# robot_sumo_easyeda.net
KiCad netlist of a schematic drawn in EasyEDA
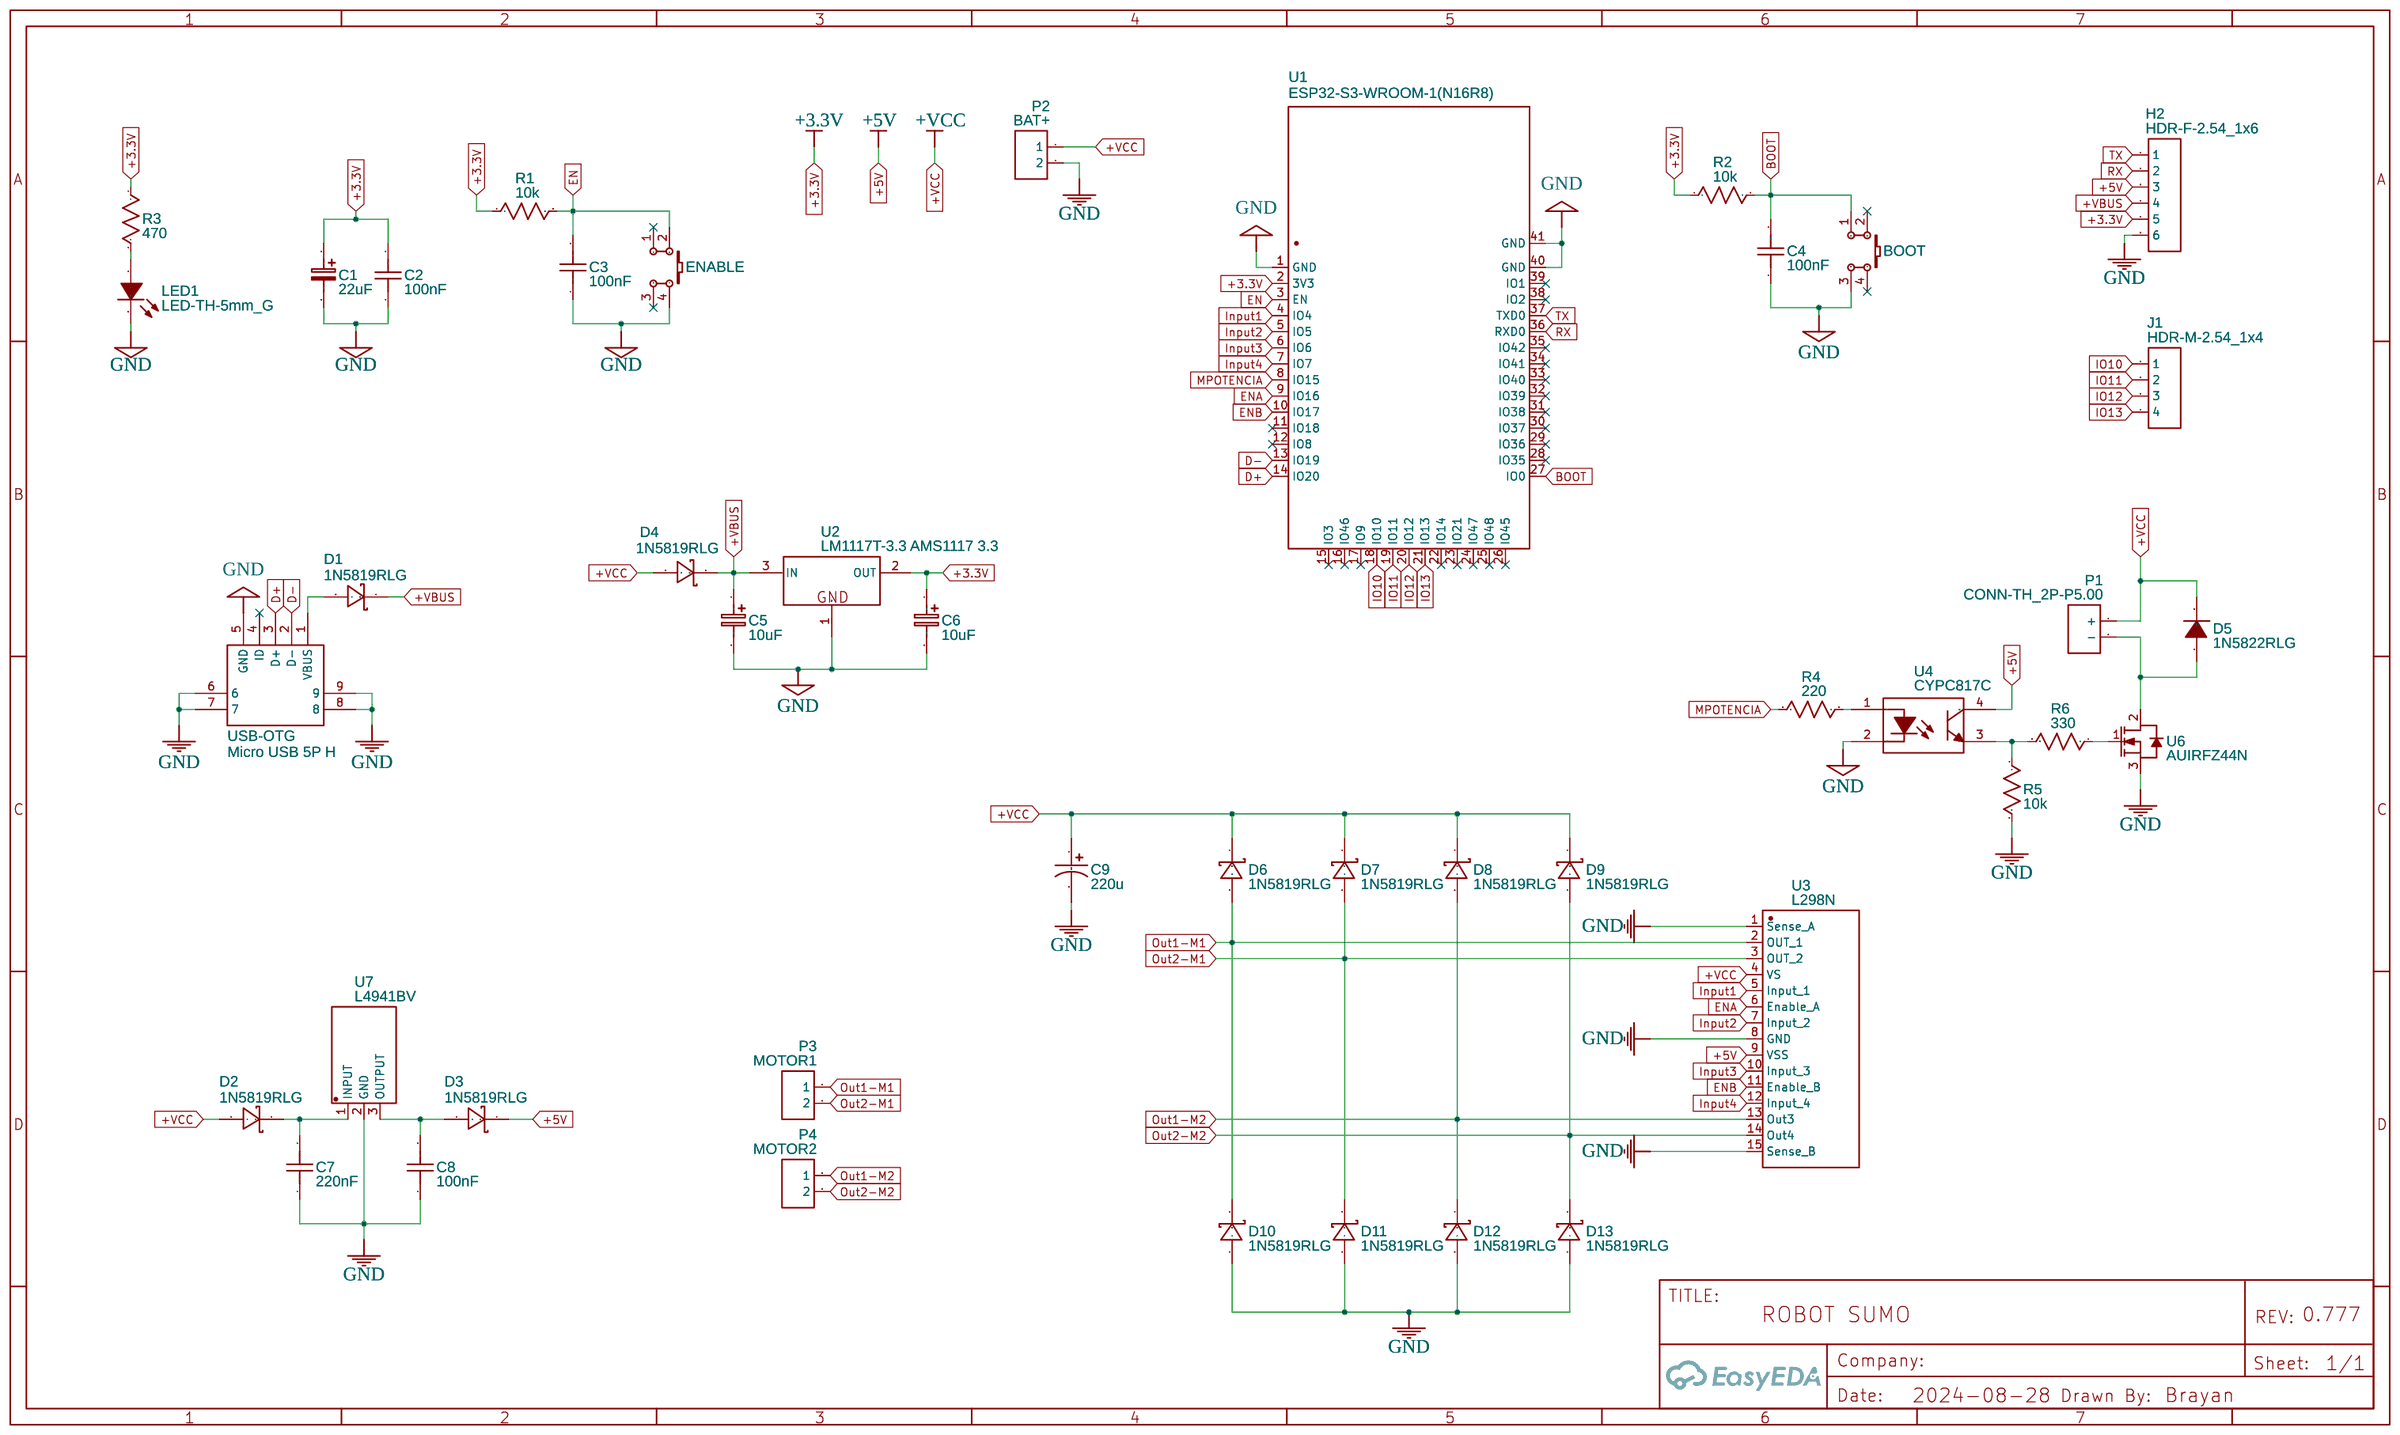
[diagram p0: schematic sheet]

(export (version "E")
  (design (tool "Eeschema 10.0.6"))
  (components
    (comp (ref "BOOT")
      (value "K4-6×6_TH")
      (fields (field (name "Manufacturer Part") "K2-1102DP-E4SW-04") (field (name "Manufacturer") "韩国韩荣"))
      (libsource (lib "") (part "K4-6×6_TH_1"))
    )
    (comp (ref "C1") (value "22uF") (libsource (lib "") (part "CE_TH_D5.0×F2.0_EU_2")))
    (comp (ref "C2")
      (value "100nF")
      (fields
        (field (name "Manufacturer Part") "CC1E104ZA1FD3F5O10MF")
        (field (name "Manufacturer") "Dersonic(德尔创)")
      )
      (libsource (lib "") (part "CC1E104ZA1FD3F5O10MF"))
    )
    (comp (ref "C3")
      (value "100nF")
      (fields
        (field (name "Manufacturer Part") "CC1E104ZA1FD3F5O10MF")
        (field (name "Manufacturer") "Dersonic(德尔创)")
      )
      (libsource (lib "") (part "CC1E104ZA1FD3F5O10MF"))
    )
    (comp (ref "C4")
      (value "100nF")
      (fields
        (field (name "Manufacturer Part") "CC1E104ZA1FD3F5O10MF")
        (field (name "Manufacturer") "Dersonic(德尔创)")
      )
      (libsource (lib "") (part "CC1E104ZA1FD3F5O10MF"))
    )
    (comp (ref "C5") (value "10uF") (libsource (lib "") (part "CE_TH_D5.0×F2.0_EU_1")))
    (comp (ref "C6") (value "10uF") (libsource (lib "") (part "CE_TH_D5.0×F2.0_EU")))
    (comp (ref "C7")
      (value "220nF")
      (fields
        (field (name "Manufacturer Part") "CC1E104ZA1FD3F5O10MF")
        (field (name "Manufacturer") "Dersonic(德尔创)")
      )
      (libsource (lib "") (part "CC1E104ZA1FD3F5O10MF"))
    )
    (comp (ref "C8")
      (value "100nF")
      (fields
        (field (name "Manufacturer Part") "CC1E104ZA1FD3F5O10MF")
        (field (name "Manufacturer") "Dersonic(德尔创)")
      )
      (libsource (lib "") (part "CC1E104ZA1FD3F5O10MF"))
    )
    (comp (ref "C9") (value "220u") (libsource (lib "") (part "CE_TH_D8.0×F3.5_US")))
    (comp (ref "D1")
      (value "1N5819RLG")
      (fields (field (name "Manufacturer") "onsemi(安森美)"))
      (libsource (lib "") (part "1N5819RLG"))
    )
    (comp (ref "D2")
      (value "1N5819RLG")
      (fields (field (name "Manufacturer") "onsemi(安森美)"))
      (libsource (lib "") (part "1N5819RLG"))
    )
    (comp (ref "D3")
      (value "1N5819RLG")
      (fields (field (name "Manufacturer") "onsemi(安森美)"))
      (libsource (lib "") (part "1N5819RLG"))
    )
    (comp (ref "D4")
      (value "1N5819RLG")
      (fields (field (name "Manufacturer") "onsemi(安森美)"))
      (libsource (lib "") (part "1N5819RLG"))
    )
    (comp (ref "D5")
      (value "1N5822RLG")
      (fields (field (name "Manufacturer") "onsemi(安森美)"))
      (libsource (lib "") (part "1N5822RLG"))
    )
    (comp (ref "D6")
      (value "1N5819RLG")
      (fields (field (name "Manufacturer") "onsemi(安森美)"))
      (libsource (lib "") (part "1N5819RLG_1"))
    )
    (comp (ref "D7")
      (value "1N5819RLG")
      (fields (field (name "Manufacturer") "onsemi(安森美)"))
      (libsource (lib "") (part "1N5819RLG_1"))
    )
    (comp (ref "D8")
      (value "1N5819RLG")
      (fields (field (name "Manufacturer") "onsemi(安森美)"))
      (libsource (lib "") (part "1N5819RLG_1"))
    )
    (comp (ref "D9")
      (value "1N5819RLG")
      (fields (field (name "Manufacturer") "onsemi(安森美)"))
      (libsource (lib "") (part "1N5819RLG_1"))
    )
    (comp (ref "D10")
      (value "1N5819RLG")
      (fields (field (name "Manufacturer") "onsemi(安森美)"))
      (libsource (lib "") (part "1N5819RLG_1"))
    )
    (comp (ref "D11")
      (value "1N5819RLG")
      (fields (field (name "Manufacturer") "onsemi(安森美)"))
      (libsource (lib "") (part "1N5819RLG_1"))
    )
    (comp (ref "D12")
      (value "1N5819RLG")
      (fields (field (name "Manufacturer") "onsemi(安森美)"))
      (libsource (lib "") (part "1N5819RLG_1"))
    )
    (comp (ref "D13")
      (value "1N5819RLG")
      (fields (field (name "Manufacturer") "onsemi(安森美)"))
      (libsource (lib "") (part "1N5819RLG_1"))
    )
    (comp (ref "ENABLE")
      (value "K4-6×6_TH")
      (fields (field (name "Manufacturer Part") "K2-1102DP-E4SW-04") (field (name "Manufacturer") "韩国韩荣"))
      (libsource (lib "") (part "K4-6×6_TH"))
    )
    (comp (ref "H2") (value "HDR-F-2.54_1x6") (libsource (lib "") (part "HDR-F-2.54_1x6")))
    (comp (ref "J1") (value "HDR-M-2.54_1x4") (libsource (lib "") (part "HDR-M-2.54_1x4")))
    (comp (ref "LED1")
      (value "LED-TH-5mm_G")
      (fields
        (field (name "Manufacturer Part") "333-2SYGD/S530-E2")
        (field (name "Manufacturer") "EVERLIGHT(台湾亿光)")
      )
      (libsource (lib "") (part "LED-TH-5mm_G"))
    )
    (comp (ref "P1") (value "CONN-TH_2P-P5.00") (libsource (lib "") (part "CONN-TH_2P-P5.00")))
    (comp (ref "P2") (value "BAT+") (libsource (lib "") (part "CONN-TH_2P-P5.00_1")))
    (comp (ref "P3") (value "MOTOR1") (libsource (lib "") (part "CONN-TH_2P-P5.00_1")))
    (comp (ref "P4") (value "MOTOR2") (libsource (lib "") (part "CONN-TH_2P-P5.00_1")))
    (comp (ref "R1") (value "10k") (libsource (lib "") (part "R_AXIAL-0.4_US_2")))
    (comp (ref "R2") (value "10k") (libsource (lib "") (part "R_AXIAL-0.4_US_2")))
    (comp (ref "R3") (value "470") (libsource (lib "") (part "R_AXIAL-0.4_US")))
    (comp (ref "R4") (value "220") (libsource (lib "") (part "R_AXIAL-0.4_US_1")))
    (comp (ref "R5") (value "10k") (libsource (lib "") (part "R_AXIAL-0.4_US")))
    (comp (ref "R6") (value "330") (libsource (lib "") (part "R_AXIAL-0.4_US_1")))
    (comp (ref "U1")
      (value "ESP32-S3-WROOM-1(N16R8)")
      (fields
        (field (name "Manufacturer Part") "ESP32-S3-WROOM-1-N16R8")
        (field (name "Manufacturer") "ESPRESSIF(乐鑫)")
      )
      (libsource (lib "") (part "ESP32-S3-WROOM-1(N16R8)"))
    )
    (comp (ref "U2")
      (value "LM1117T-3.3 AMS1117 3.3")
      (fields (field (name "Manufacturer Part") "LM1117T-3.3") (field (name "Manufacturer") "HGSEMI(华冠)"))
      (libsource (lib "") (part "LM1117T-3.3"))
    )
    (comp (ref "U3")
      (value "L298N")
      (fields (field (name "Manufacturer") "HGSEMI(华冠)"))
      (libsource (lib "") (part "L298N"))
    )
    (comp (ref "U4")
      (value "CYPC817C")
      (fields (field (name "Manufacturer") "OCIC(卓睿科)"))
      (libsource (lib "") (part "CYPC817C"))
    )
    (comp (ref "U6")
      (value "AUIRFZ44N")
      (fields (field (name "Manufacturer") "Infineon(英飞凌)"))
      (libsource (lib "") (part "AUIRFZ44N"))
    )
    (comp (ref "U7")
      (value "L4941BV")
      (fields (field (name "Manufacturer") "ST(意法半导体)"))
      (libsource (lib "") (part "L4941BV"))
    )
    (comp (ref "USB-OTG")
      (value "Micro USB 5P H")
      (fields (field (name "Manufacturer Part") "920-E52A2021S10101") (field (name "Manufacturer") "精拓金"))
      (libsource (lib "") (part "Micro USB 5P H"))
    )
  )
  (nets
    (net (code "1") (name "+3.3V") (class "Default")
      (node (ref "C1") (pin "1") (pinfunction "1_1") (pintype "unspecified"))
      (node (ref "C2") (pin "2") (pinfunction "2_2") (pintype "unspecified"))
      (node (ref "C6") (pin "1") (pinfunction "1_1") (pintype "unspecified"))
      (node (ref "H2") (pin "5") (pinfunction "5_5") (pintype "input"))
      (node (ref "R1") (pin "1") (pinfunction "1_1") (pintype "unspecified"))
      (node (ref "R2") (pin "1") (pinfunction "1_1") (pintype "unspecified"))
      (node (ref "R3") (pin "1") (pinfunction "1_1") (pintype "unspecified"))
      (node (ref "U1") (pin "2") (pinfunction "3V3_2") (pintype "unspecified"))
      (node (ref "U2") (pin "2") (pinfunction "OUT_2") (pintype "unspecified"))
    )
    (net (code "2") (name "+5V") (class "Default")
      (node (ref "D3") (pin "1") (pinfunction "C_1") (pintype "unspecified"))
      (node (ref "H2") (pin "3") (pinfunction "3_3") (pintype "input"))
      (node (ref "U3") (pin "9") (pinfunction "VSS_9") (pintype "unspecified"))
      (node (ref "U4") (pin "4") (pinfunction "COL_4") (pintype "unspecified"))
    )
    (net (code "3") (name "+VBUS") (class "Default")
      (node (ref "C5") (pin "1") (pinfunction "1_1") (pintype "unspecified"))
      (node (ref "D1") (pin "1") (pinfunction "C_1") (pintype "unspecified"))
      (node (ref "D4") (pin "1") (pinfunction "C_1") (pintype "unspecified"))
      (node (ref "H2") (pin "4") (pinfunction "4_4") (pintype "input"))
      (node (ref "U2") (pin "3") (pinfunction "IN_3") (pintype "unspecified"))
    )
    (net (code "4") (name "+VCC") (class "Default")
      (node (ref "C9") (pin "1") (pinfunction "1_1") (pintype "unspecified"))
      (node (ref "D2") (pin "2") (pinfunction "A_2") (pintype "unspecified"))
      (node (ref "D4") (pin "2") (pinfunction "A_2") (pintype "unspecified"))
      (node (ref "D5") (pin "1") (pinfunction "C_1") (pintype "unspecified"))
      (node (ref "D6") (pin "1") (pinfunction "C_1") (pintype "unspecified"))
      (node (ref "D7") (pin "1") (pinfunction "C_1") (pintype "unspecified"))
      (node (ref "D8") (pin "1") (pinfunction "C_1") (pintype "unspecified"))
      (node (ref "D9") (pin "1") (pinfunction "C_1") (pintype "unspecified"))
      (node (ref "P1") (pin "1") (pinfunction "+_1") (pintype "unspecified"))
      (node (ref "P2") (pin "1") (pinfunction "1_1") (pintype "unspecified"))
      (node (ref "U3") (pin "4") (pinfunction "VS_4") (pintype "unspecified"))
    )
    (net (code "5") (name "BOOT") (class "Default")
      (node (ref "BOOT") (pin "1") (pinfunction "1_1") (pintype "unspecified"))
      (node (ref "C4") (pin "2") (pinfunction "2_2") (pintype "unspecified"))
      (node (ref "R2") (pin "2") (pinfunction "2_2") (pintype "unspecified"))
      (node (ref "U1") (pin "27") (pinfunction "IO0_27") (pintype "unspecified"))
    )
    (net (code "6") (name "D+") (class "Default")
      (node (ref "U1") (pin "14") (pinfunction "IO20_14") (pintype "unspecified"))
      (node (ref "USB-OTG") (pin "3") (pinfunction "D+_3") (pintype "unspecified"))
    )
    (net (code "7") (name "D-") (class "Default")
      (node (ref "U1") (pin "13") (pinfunction "IO19_13") (pintype "unspecified"))
      (node (ref "USB-OTG") (pin "2") (pinfunction "D-_2") (pintype "unspecified"))
    )
    (net (code "8") (name "EN") (class "Default")
      (node (ref "C3") (pin "2") (pinfunction "2_2") (pintype "unspecified"))
      (node (ref "ENABLE") (pin "2") (pinfunction "2_2") (pintype "unspecified"))
      (node (ref "R1") (pin "2") (pinfunction "2_2") (pintype "unspecified"))
      (node (ref "U1") (pin "3") (pinfunction "EN_3") (pintype "unspecified"))
    )
    (net (code "9") (name "ENA") (class "Default")
      (node (ref "U1") (pin "9") (pinfunction "IO16_9") (pintype "unspecified"))
      (node (ref "U3") (pin "6") (pinfunction "Enable_A_6") (pintype "unspecified"))
    )
    (net (code "10") (name "ENB") (class "Default")
      (node (ref "U1") (pin "10") (pinfunction "IO17_10") (pintype "unspecified"))
      (node (ref "U3") (pin "11") (pinfunction "Enable_B_11") (pintype "unspecified"))
    )
    (net (code "11") (name "GND") (class "Default")
      (node (ref "BOOT") (pin "3") (pinfunction "3_3") (pintype "unspecified"))
      (node (ref "C1") (pin "2") (pinfunction "2_2") (pintype "unspecified"))
      (node (ref "C2") (pin "1") (pinfunction "1_1") (pintype "unspecified"))
      (node (ref "C3") (pin "1") (pinfunction "1_1") (pintype "unspecified"))
      (node (ref "C4") (pin "1") (pinfunction "1_1") (pintype "unspecified"))
      (node (ref "C5") (pin "2") (pinfunction "2_2") (pintype "unspecified"))
      (node (ref "C6") (pin "2") (pinfunction "2_2") (pintype "unspecified"))
      (node (ref "C7") (pin "1") (pinfunction "1_1") (pintype "unspecified"))
      (node (ref "C8") (pin "1") (pinfunction "1_1") (pintype "unspecified"))
      (node (ref "C9") (pin "2") (pinfunction "2_2") (pintype "unspecified"))
      (node (ref "D10") (pin "2") (pinfunction "A_2") (pintype "unspecified"))
      (node (ref "D11") (pin "2") (pinfunction "A_2") (pintype "unspecified"))
      (node (ref "D12") (pin "2") (pinfunction "A_2") (pintype "unspecified"))
      (node (ref "D13") (pin "2") (pinfunction "A_2") (pintype "unspecified"))
      (node (ref "ENABLE") (pin "4") (pinfunction "4_4") (pintype "unspecified"))
      (node (ref "H2") (pin "6") (pinfunction "6_6") (pintype "input"))
      (node (ref "LED1") (pin "2") (pinfunction "2_2") (pintype "unspecified"))
      (node (ref "P2") (pin "2") (pinfunction "2_2") (pintype "unspecified"))
      (node (ref "R5") (pin "2") (pinfunction "2_2") (pintype "unspecified"))
      (node (ref "U1") (pin "1") (pinfunction "GND_1") (pintype "unspecified"))
      (node (ref "U1") (pin "40") (pinfunction "GND_40") (pintype "unspecified"))
      (node (ref "U1") (pin "41") (pinfunction "GND_41") (pintype "unspecified"))
      (node (ref "U2") (pin "1") (pinfunction "GND_1") (pintype "unspecified"))
      (node (ref "U3") (pin "1") (pinfunction "Sense_A_1") (pintype "unspecified"))
      (node (ref "U3") (pin "15") (pinfunction "Sense_B_15") (pintype "unspecified"))
      (node (ref "U3") (pin "8") (pinfunction "GND_8") (pintype "unspecified"))
      (node (ref "U4") (pin "2") (pinfunction "CAT_2") (pintype "unspecified"))
      (node (ref "U6") (pin "3") (pinfunction "S_3") (pintype "unspecified"))
      (node (ref "U7") (pin "2") (pinfunction "GND_2") (pintype "unspecified"))
      (node (ref "USB-OTG") (pin "5") (pinfunction "GND_5") (pintype "unspecified"))
      (node (ref "USB-OTG") (pin "6") (pinfunction "6_6") (pintype "unspecified"))
      (node (ref "USB-OTG") (pin "7") (pinfunction "7_7") (pintype "unspecified"))
      (node (ref "USB-OTG") (pin "8") (pinfunction "8_8") (pintype "unspecified"))
      (node (ref "USB-OTG") (pin "9") (pinfunction "9_9") (pintype "unspecified"))
    )
    (net (code "12") (name "IO10") (class "Default")
      (node (ref "J1") (pin "1") (pinfunction "1_1") (pintype "unspecified"))
      (node (ref "U1") (pin "18") (pinfunction "IO10_18") (pintype "unspecified"))
    )
    (net (code "13") (name "IO11") (class "Default")
      (node (ref "J1") (pin "2") (pinfunction "2_2") (pintype "unspecified"))
      (node (ref "U1") (pin "19") (pinfunction "IO11_19") (pintype "unspecified"))
    )
    (net (code "14") (name "IO12") (class "Default")
      (node (ref "J1") (pin "3") (pinfunction "3_3") (pintype "unspecified"))
      (node (ref "U1") (pin "20") (pinfunction "IO12_20") (pintype "unspecified"))
    )
    (net (code "15") (name "IO13") (class "Default")
      (node (ref "J1") (pin "4") (pinfunction "4_4") (pintype "unspecified"))
      (node (ref "U1") (pin "21") (pinfunction "IO13_21") (pintype "unspecified"))
    )
    (net (code "16") (name "Input1") (class "Default")
      (node (ref "U1") (pin "4") (pinfunction "IO4_4") (pintype "unspecified"))
      (node (ref "U3") (pin "5") (pinfunction "Input_1_5") (pintype "unspecified"))
    )
    (net (code "17") (name "Input2") (class "Default")
      (node (ref "U1") (pin "5") (pinfunction "IO5_5") (pintype "unspecified"))
      (node (ref "U3") (pin "7") (pinfunction "Input_2_7") (pintype "unspecified"))
    )
    (net (code "18") (name "Input3") (class "Default")
      (node (ref "U1") (pin "6") (pinfunction "IO6_6") (pintype "unspecified"))
      (node (ref "U3") (pin "10") (pinfunction "Input_3_10") (pintype "unspecified"))
    )
    (net (code "19") (name "Input4") (class "Default")
      (node (ref "U1") (pin "7") (pinfunction "IO7_7") (pintype "unspecified"))
      (node (ref "U3") (pin "12") (pinfunction "Input_4_12") (pintype "unspecified"))
    )
    (net (code "20") (name "MPOTENCIA") (class "Default")
      (node (ref "R4") (pin "2") (pinfunction "2_2") (pintype "unspecified"))
      (node (ref "U1") (pin "8") (pinfunction "IO15_8") (pintype "unspecified"))
    )
    (net (code "21") (name "Net-(D1-A)") (class "Default")
      (node (ref "D1") (pin "2") (pinfunction "A_2") (pintype "unspecified"))
      (node (ref "USB-OTG") (pin "1") (pinfunction "VBUS_1") (pintype "unspecified"))
    )
    (net (code "22") (name "Net-(D2-C)") (class "Default")
      (node (ref "C7") (pin "2") (pinfunction "2_2") (pintype "unspecified"))
      (node (ref "D2") (pin "1") (pinfunction "C_1") (pintype "unspecified"))
      (node (ref "U7") (pin "1") (pinfunction "INPUT_1") (pintype "unspecified"))
    )
    (net (code "23") (name "Net-(D3-A)") (class "Default")
      (node (ref "C8") (pin "2") (pinfunction "2_2") (pintype "unspecified"))
      (node (ref "D3") (pin "2") (pinfunction "A_2") (pintype "unspecified"))
      (node (ref "U7") (pin "3") (pinfunction "OUTPUT_3") (pintype "unspecified"))
    )
    (net (code "24") (name "Net-(D5-A)") (class "Default")
      (node (ref "D5") (pin "2") (pinfunction "A_2") (pintype "unspecified"))
      (node (ref "P1") (pin "2") (pinfunction "-_2") (pintype "unspecified"))
      (node (ref "U6") (pin "2") (pinfunction "D_2") (pintype "unspecified"))
    )
    (net (code "25") (name "Net-(LED1-Pad1)") (class "Default")
      (node (ref "LED1") (pin "1") (pinfunction "1_1") (pintype "unspecified"))
      (node (ref "R3") (pin "2") (pinfunction "2_2") (pintype "unspecified"))
    )
    (net (code "26") (name "Net-(U4-AN)") (class "Default")
      (node (ref "R4") (pin "1") (pinfunction "1_1") (pintype "unspecified"))
      (node (ref "U4") (pin "1") (pinfunction "AN_1") (pintype "unspecified"))
    )
    (net (code "27") (name "Net-(U4-EMI)") (class "Default")
      (node (ref "R5") (pin "1") (pinfunction "1_1") (pintype "unspecified"))
      (node (ref "R6") (pin "2") (pinfunction "2_2") (pintype "unspecified"))
      (node (ref "U4") (pin "3") (pinfunction "EMI_3") (pintype "unspecified"))
    )
    (net (code "28") (name "Net-(U6-G)") (class "Default")
      (node (ref "R6") (pin "1") (pinfunction "1_1") (pintype "unspecified"))
      (node (ref "U6") (pin "1") (pinfunction "G_1") (pintype "unspecified"))
    )
    (net (code "29") (name "Out1-M1") (class "Default")
      (node (ref "D10") (pin "1") (pinfunction "C_1") (pintype "unspecified"))
      (node (ref "D6") (pin "2") (pinfunction "A_2") (pintype "unspecified"))
      (node (ref "P3") (pin "1") (pinfunction "1_1") (pintype "unspecified"))
      (node (ref "U3") (pin "2") (pinfunction "OUT_1_2") (pintype "unspecified"))
    )
    (net (code "30") (name "Out1-M2") (class "Default")
      (node (ref "D12") (pin "1") (pinfunction "C_1") (pintype "unspecified"))
      (node (ref "D8") (pin "2") (pinfunction "A_2") (pintype "unspecified"))
      (node (ref "P4") (pin "1") (pinfunction "1_1") (pintype "unspecified"))
      (node (ref "U3") (pin "13") (pinfunction "Out3_13") (pintype "unspecified"))
    )
    (net (code "31") (name "Out2-M1") (class "Default")
      (node (ref "D11") (pin "1") (pinfunction "C_1") (pintype "unspecified"))
      (node (ref "D7") (pin "2") (pinfunction "A_2") (pintype "unspecified"))
      (node (ref "P3") (pin "2") (pinfunction "2_2") (pintype "unspecified"))
      (node (ref "U3") (pin "3") (pinfunction "OUT_2_3") (pintype "unspecified"))
    )
    (net (code "32") (name "Out2-M2") (class "Default")
      (node (ref "D13") (pin "1") (pinfunction "C_1") (pintype "unspecified"))
      (node (ref "D9") (pin "2") (pinfunction "A_2") (pintype "unspecified"))
      (node (ref "P4") (pin "2") (pinfunction "2_2") (pintype "unspecified"))
      (node (ref "U3") (pin "14") (pinfunction "Out4_14") (pintype "unspecified"))
    )
    (net (code "33") (name "RX") (class "Default")
      (node (ref "H2") (pin "2") (pinfunction "2_2") (pintype "input"))
      (node (ref "U1") (pin "36") (pinfunction "RXD0_36") (pintype "unspecified"))
    )
    (net (code "34") (name "TX") (class "Default")
      (node (ref "H2") (pin "1") (pinfunction "1_1") (pintype "input"))
      (node (ref "U1") (pin "37") (pinfunction "TXD0_37") (pintype "unspecified"))
    )
    (net (code "35") (name "unconnected-(BOOT-Pad2)") (class "Default")
      (node (ref "BOOT") (pin "2") (pinfunction "2_2") (pintype "unspecified+no_connect"))
    )
    (net (code "36") (name "unconnected-(BOOT-Pad4)") (class "Default")
      (node (ref "BOOT") (pin "4") (pinfunction "4_4") (pintype "unspecified+no_connect"))
    )
    (net (code "37") (name "unconnected-(ENABLE-Pad1)") (class "Default")
      (node (ref "ENABLE") (pin "1") (pinfunction "1_1") (pintype "unspecified+no_connect"))
    )
    (net (code "38") (name "unconnected-(ENABLE-Pad3)") (class "Default")
      (node (ref "ENABLE") (pin "3") (pinfunction "3_3") (pintype "unspecified+no_connect"))
    )
    (net (code "39") (name "unconnected-(U1-IO1-Pad39)") (class "Default")
      (node (ref "U1") (pin "39") (pinfunction "IO1_39") (pintype "unspecified+no_connect"))
    )
    (net (code "40") (name "unconnected-(U1-IO2-Pad38)") (class "Default")
      (node (ref "U1") (pin "38") (pinfunction "IO2_38") (pintype "unspecified+no_connect"))
    )
    (net (code "41") (name "unconnected-(U1-IO3-Pad15)") (class "Default")
      (node (ref "U1") (pin "15") (pinfunction "IO3_15") (pintype "unspecified+no_connect"))
    )
    (net (code "42") (name "unconnected-(U1-IO8-Pad12)") (class "Default")
      (node (ref "U1") (pin "12") (pinfunction "IO8_12") (pintype "unspecified+no_connect"))
    )
    (net (code "43") (name "unconnected-(U1-IO9-Pad17)") (class "Default")
      (node (ref "U1") (pin "17") (pinfunction "IO9_17") (pintype "unspecified+no_connect"))
    )
    (net (code "44") (name "unconnected-(U1-IO14-Pad22)") (class "Default")
      (node (ref "U1") (pin "22") (pinfunction "IO14_22") (pintype "unspecified+no_connect"))
    )
    (net (code "45") (name "unconnected-(U1-IO18-Pad11)") (class "Default")
      (node (ref "U1") (pin "11") (pinfunction "IO18_11") (pintype "unspecified+no_connect"))
    )
    (net (code "46") (name "unconnected-(U1-IO21-Pad23)") (class "Default")
      (node (ref "U1") (pin "23") (pinfunction "IO21_23") (pintype "unspecified+no_connect"))
    )
    (net (code "47") (name "unconnected-(U1-IO35-Pad28)") (class "Default")
      (node (ref "U1") (pin "28") (pinfunction "IO35_28") (pintype "unspecified+no_connect"))
    )
    (net (code "48") (name "unconnected-(U1-IO36-Pad29)") (class "Default")
      (node (ref "U1") (pin "29") (pinfunction "IO36_29") (pintype "unspecified+no_connect"))
    )
    (net (code "49") (name "unconnected-(U1-IO37-Pad30)") (class "Default")
      (node (ref "U1") (pin "30") (pinfunction "IO37_30") (pintype "unspecified+no_connect"))
    )
    (net (code "50") (name "unconnected-(U1-IO38-Pad31)") (class "Default")
      (node (ref "U1") (pin "31") (pinfunction "IO38_31") (pintype "unspecified+no_connect"))
    )
    (net (code "51") (name "unconnected-(U1-IO39-Pad32)") (class "Default")
      (node (ref "U1") (pin "32") (pinfunction "IO39_32") (pintype "unspecified+no_connect"))
    )
    (net (code "52") (name "unconnected-(U1-IO40-Pad33)") (class "Default")
      (node (ref "U1") (pin "33") (pinfunction "IO40_33") (pintype "unspecified+no_connect"))
    )
    (net (code "53") (name "unconnected-(U1-IO41-Pad34)") (class "Default")
      (node (ref "U1") (pin "34") (pinfunction "IO41_34") (pintype "unspecified+no_connect"))
    )
    (net (code "54") (name "unconnected-(U1-IO42-Pad35)") (class "Default")
      (node (ref "U1") (pin "35") (pinfunction "IO42_35") (pintype "unspecified+no_connect"))
    )
    (net (code "55") (name "unconnected-(U1-IO45-Pad26)") (class "Default")
      (node (ref "U1") (pin "26") (pinfunction "IO45_26") (pintype "unspecified+no_connect"))
    )
    (net (code "56") (name "unconnected-(U1-IO46-Pad16)") (class "Default")
      (node (ref "U1") (pin "16") (pinfunction "IO46_16") (pintype "unspecified+no_connect"))
    )
    (net (code "57") (name "unconnected-(U1-IO47-Pad24)") (class "Default")
      (node (ref "U1") (pin "24") (pinfunction "IO47_24") (pintype "unspecified+no_connect"))
    )
    (net (code "58") (name "unconnected-(U1-IO48-Pad25)") (class "Default")
      (node (ref "U1") (pin "25") (pinfunction "IO48_25") (pintype "unspecified+no_connect"))
    )
    (net (code "59") (name "unconnected-(USB-OTG-ID-Pad4)") (class "Default")
      (node (ref "USB-OTG") (pin "4") (pinfunction "ID_4") (pintype "unspecified+no_connect"))
    )
  )
)
